# A502D.net
KiCad netlist of a schematic drawn in EAGLE
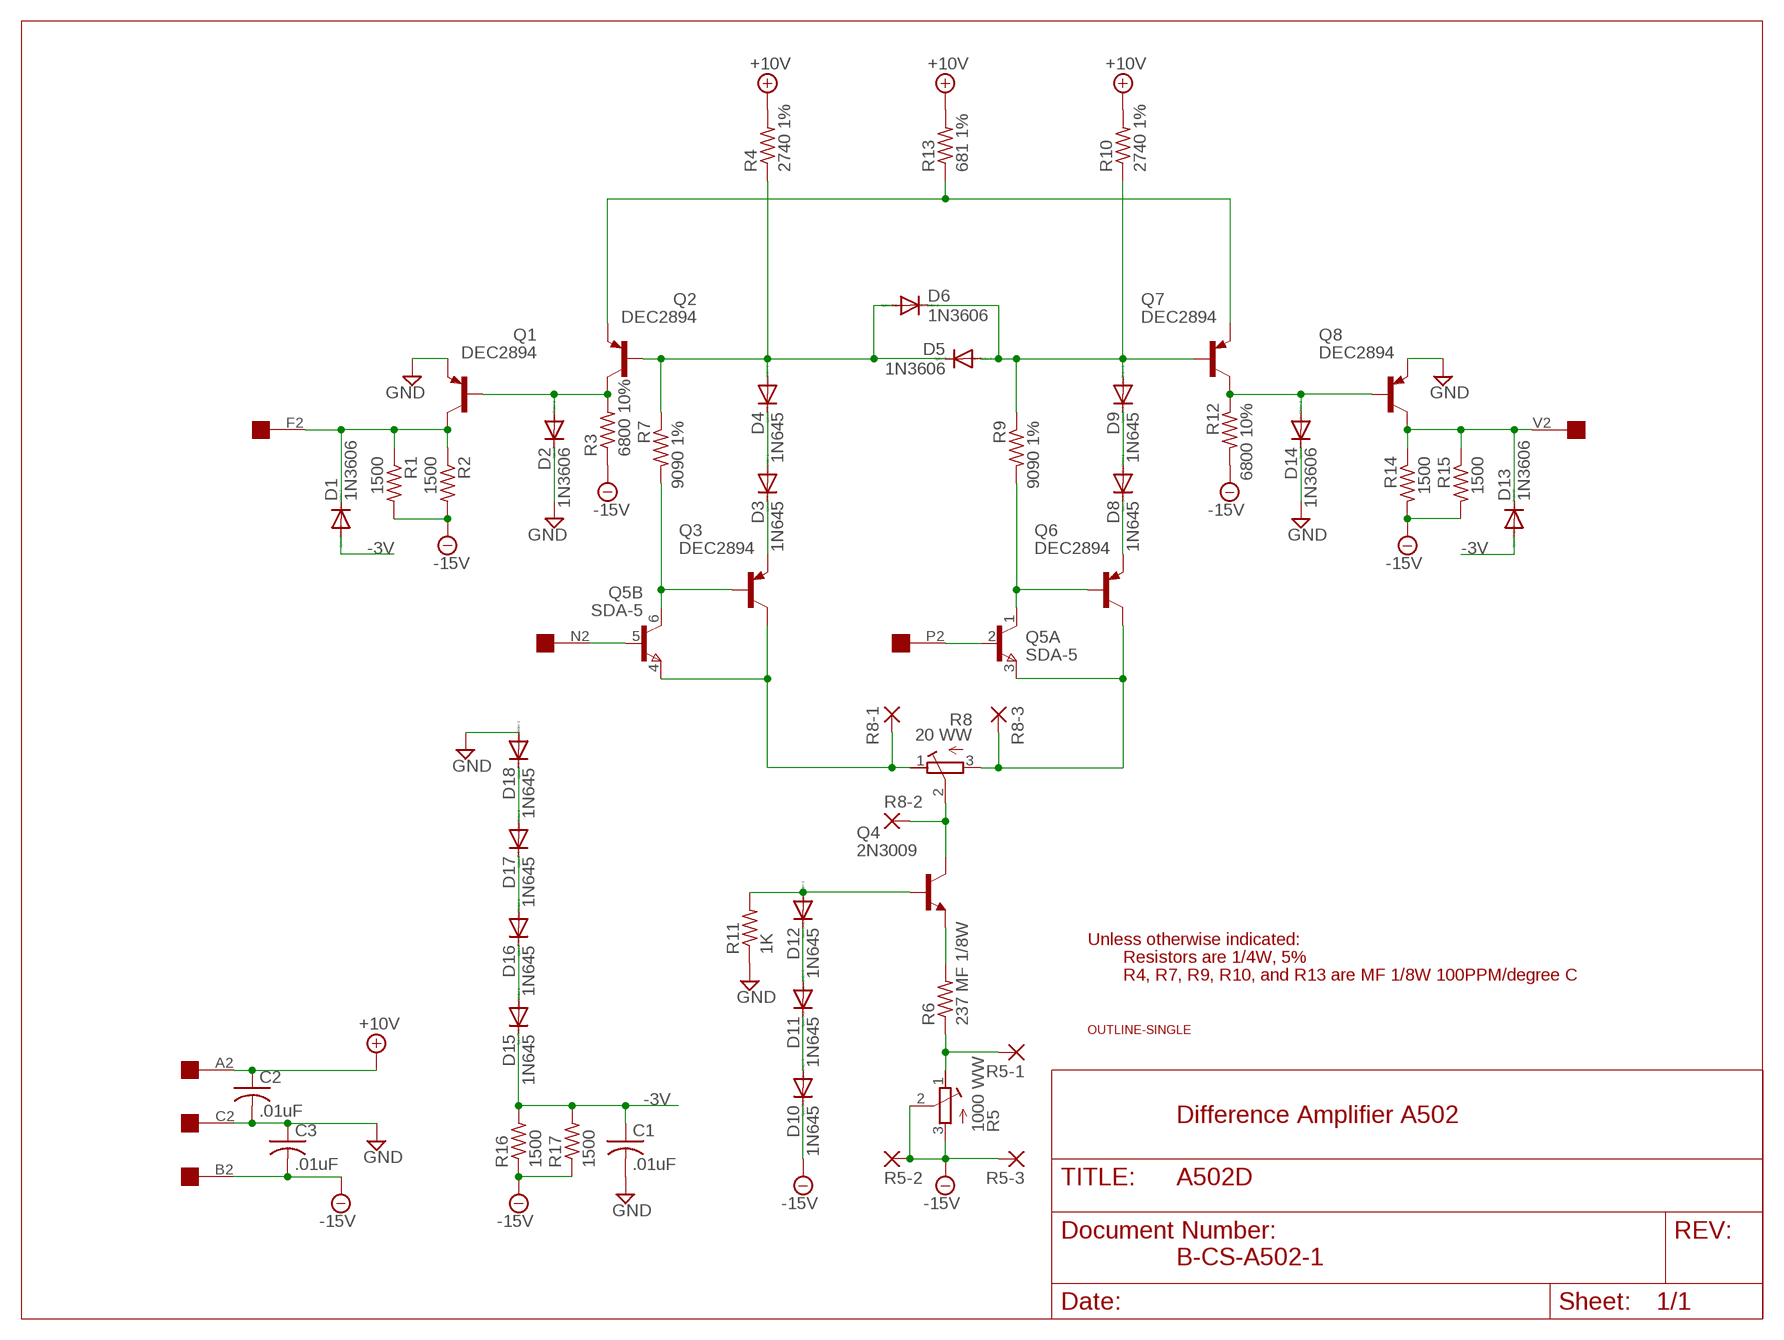
[diagram p0: schematic, sheet 1]

(export (version "E")
  (design (tool "Eeschema 10.0.6"))
  (components
    (comp (ref "C1")
      (value ".01uF")
      (footprint "eagle-import:C050-025X075")
      (libsource (lib "eagle-import") (part "C-US050-025X075"))
    )
    (comp (ref "C2")
      (value ".01uF")
      (footprint "eagle-import:C050-025X075")
      (libsource (lib "eagle-import") (part "C-US050-025X075"))
    )
    (comp (ref "C3")
      (value ".01uF")
      (footprint "eagle-import:C050-025X075")
      (libsource (lib "eagle-import") (part "C-US050-025X075"))
    )
    (comp (ref "D1")
      (value "1N3606")
      (footprint "eagle-import:DO35-10")
      (libsource (lib "eagle-import") (part "1N4148DO35-10"))
    )
    (comp (ref "D2")
      (value "1N3606")
      (footprint "eagle-import:DO35-10")
      (libsource (lib "eagle-import") (part "1N4148DO35-10"))
    )
    (comp (ref "D3")
      (value "1N645")
      (footprint "eagle-import:DO35-10")
      (libsource (lib "eagle-import") (part "1N4148DO35-10"))
    )
    (comp (ref "D4")
      (value "1N645")
      (footprint "eagle-import:DO35-10")
      (libsource (lib "eagle-import") (part "1N4148DO35-10"))
    )
    (comp (ref "D5")
      (value "1N3606")
      (footprint "eagle-import:DO35-10")
      (libsource (lib "eagle-import") (part "1N4148DO35-10"))
    )
    (comp (ref "D6")
      (value "1N3606")
      (footprint "eagle-import:DO35-10")
      (libsource (lib "eagle-import") (part "1N4148DO35-10"))
    )
    (comp (ref "D8")
      (value "1N645")
      (footprint "eagle-import:DO35-10")
      (libsource (lib "eagle-import") (part "1N4148DO35-10"))
    )
    (comp (ref "D9")
      (value "1N645")
      (footprint "eagle-import:DO35-10")
      (libsource (lib "eagle-import") (part "1N4148DO35-10"))
    )
    (comp (ref "D10")
      (value "1N645")
      (footprint "eagle-import:DO35-10")
      (libsource (lib "eagle-import") (part "1N4148DO35-10"))
    )
    (comp (ref "D11")
      (value "1N645")
      (footprint "eagle-import:DO35-10")
      (libsource (lib "eagle-import") (part "1N4148DO35-10"))
    )
    (comp (ref "D12")
      (value "1N645")
      (footprint "eagle-import:DO35-10")
      (libsource (lib "eagle-import") (part "1N4148DO35-10"))
    )
    (comp (ref "D13")
      (value "1N3606")
      (footprint "eagle-import:DO35-10")
      (libsource (lib "eagle-import") (part "1N4148DO35-10"))
    )
    (comp (ref "D14")
      (value "1N3606")
      (footprint "eagle-import:DO35-10")
      (libsource (lib "eagle-import") (part "1N4148DO35-10"))
    )
    (comp (ref "D15")
      (value "1N645")
      (footprint "eagle-import:DO35-10")
      (libsource (lib "eagle-import") (part "1N4148DO35-10"))
    )
    (comp (ref "D16")
      (value "1N645")
      (footprint "eagle-import:DO35-10")
      (libsource (lib "eagle-import") (part "1N4148DO35-10"))
    )
    (comp (ref "D17")
      (value "1N645")
      (footprint "eagle-import:DO35-10")
      (libsource (lib "eagle-import") (part "1N4148DO35-10"))
    )
    (comp (ref "D18")
      (value "1N645")
      (footprint "eagle-import:DO35-10")
      (libsource (lib "eagle-import") (part "1N4148DO35-10"))
    )
    (comp (ref "Q1")
      (value "DEC2894")
      (footprint "eagle-import:TO39")
      (libsource (lib "eagle-import") (part "2N2904A"))
    )
    (comp (ref "Q2")
      (value "DEC2894")
      (footprint "eagle-import:TO39")
      (libsource (lib "eagle-import") (part "2N2904A"))
    )
    (comp (ref "Q3")
      (value "DEC2894")
      (footprint "eagle-import:TO39")
      (libsource (lib "eagle-import") (part "2N2904A"))
    )
    (comp (ref "Q4")
      (value "2N3009")
      (footprint "eagle-import:TO5")
      (libsource (lib "eagle-import") (part "2N2219"))
    )
    (comp (ref "Q5")
      (value "SDA-5")
      (footprint "eagle-import:TO78")
      (libsource (lib "eagle-import") (part "MAT-02H"))
    )
    (comp (ref "Q6")
      (value "DEC2894")
      (footprint "eagle-import:TO39")
      (libsource (lib "eagle-import") (part "2N2904A"))
    )
    (comp (ref "Q7")
      (value "DEC2894")
      (footprint "eagle-import:TO39")
      (libsource (lib "eagle-import") (part "2N2904A"))
    )
    (comp (ref "Q8")
      (value "DEC2894")
      (footprint "eagle-import:TO39")
      (libsource (lib "eagle-import") (part "2N2904A"))
    )
    (comp (ref "R1")
      (value "1500")
      (footprint "eagle-import:0207_10")
      (libsource (lib "eagle-import") (part "R-US_0207/10"))
    )
    (comp (ref "R2")
      (value "1500")
      (footprint "eagle-import:0207_10")
      (libsource (lib "eagle-import") (part "R-US_0207/10"))
    )
    (comp (ref "R3")
      (value "6800 10%")
      (footprint "eagle-import:0207_10")
      (libsource (lib "eagle-import") (part "R-US_0207/10"))
    )
    (comp (ref "R4")
      (value "2740 1%")
      (footprint "eagle-import:0207_15")
      (libsource (lib "eagle-import") (part "R-US_0207/15"))
    )
    (comp (ref "R5")
      (value "1000 WW")
      (footprint "eagle-import:3006Y")
      (libsource (lib "eagle-import") (part "275P"))
    )
    (comp (ref "R5-1")
      (value "2,54/0,8")
      (footprint "eagle-import:2,54_0,8")
      (libsource (lib "eagle-import") (part "2,54/0,8"))
    )
    (comp (ref "R5-2")
      (value "2,54/0,8")
      (footprint "eagle-import:2,54_0,8")
      (libsource (lib "eagle-import") (part "2,54/0,8"))
    )
    (comp (ref "R5-3")
      (value "2,54/0,8")
      (footprint "eagle-import:2,54_0,8")
      (libsource (lib "eagle-import") (part "2,54/0,8"))
    )
    (comp (ref "R6")
      (value "237 MF 1/8W")
      (footprint "eagle-import:0207_15")
      (libsource (lib "eagle-import") (part "R-US_0207/15"))
    )
    (comp (ref "R7")
      (value "9090 1%")
      (footprint "eagle-import:0207_15")
      (libsource (lib "eagle-import") (part "R-US_0207/15"))
    )
    (comp (ref "R8")
      (value "20 WW")
      (footprint "eagle-import:3006Y")
      (libsource (lib "eagle-import") (part "275P"))
    )
    (comp (ref "R8-1")
      (value "2,54/0,8")
      (footprint "eagle-import:2,54_0,8")
      (libsource (lib "eagle-import") (part "2,54/0,8"))
    )
    (comp (ref "R8-2")
      (value "2,54/0,8")
      (footprint "eagle-import:2,54_0,8")
      (libsource (lib "eagle-import") (part "2,54/0,8"))
    )
    (comp (ref "R8-3")
      (value "2,54/0,8")
      (footprint "eagle-import:2,54_0,8")
      (libsource (lib "eagle-import") (part "2,54/0,8"))
    )
    (comp (ref "R9")
      (value "9090 1%")
      (footprint "eagle-import:0207_15")
      (libsource (lib "eagle-import") (part "R-US_0207/15"))
    )
    (comp (ref "R10")
      (value "2740 1%")
      (footprint "eagle-import:0207_15")
      (libsource (lib "eagle-import") (part "R-US_0207/15"))
    )
    (comp (ref "R11")
      (value "1K")
      (footprint "eagle-import:0207_10")
      (libsource (lib "eagle-import") (part "R-US_0207/10"))
    )
    (comp (ref "R12")
      (value "6800 10%")
      (footprint "eagle-import:0207_10")
      (libsource (lib "eagle-import") (part "R-US_0207/10"))
    )
    (comp (ref "R13")
      (value "681 1%")
      (footprint "eagle-import:0207_15")
      (libsource (lib "eagle-import") (part "R-US_0207/15"))
    )
    (comp (ref "R14")
      (value "1500")
      (footprint "eagle-import:0207_10")
      (libsource (lib "eagle-import") (part "R-US_0207/10"))
    )
    (comp (ref "R15")
      (value "1500")
      (footprint "eagle-import:0207_10")
      (libsource (lib "eagle-import") (part "R-US_0207/10"))
    )
    (comp (ref "R16")
      (value "1500")
      (footprint "eagle-import:0207_10")
      (libsource (lib "eagle-import") (part "R-US_0207/10"))
    )
    (comp (ref "R17")
      (value "1500")
      (footprint "eagle-import:0207_10")
      (libsource (lib "eagle-import") (part "R-US_0207/10"))
    )
    (comp (ref "U$2")
      (value "OUTLINE-SINGLE")
      (footprint "eagle-import:SINGLE")
      (libsource (lib "eagle-import") (part "OUTLINE-SINGLE"))
    )
    (comp (ref "U$3")
      (value "EDGE-1")
      (footprint "eagle-import:EDGE-CON1")
      (libsource (lib "eagle-import") (part "EDGE-1"))
    )
  )
  (nets
    (net (code "1") (name "+10V") (class "Default")
      (node (ref "C2") (pin "1") (pinfunction "1_1") (pintype "passive"))
      (node (ref "R10") (pin "2") (pinfunction "2_2") (pintype "passive"))
      (node (ref "R13") (pin "2") (pinfunction "2_2") (pintype "passive"))
      (node (ref "R4") (pin "2") (pinfunction "2_2") (pintype "passive"))
      (node (ref "U$3") (pin "A2") (pinfunction "1_A2") (pintype "bidirectional"))
    )
    (net (code "2") (name "-15V") (class "Default")
      (node (ref "C3") (pin "2") (pinfunction "2_2") (pintype "passive"))
      (node (ref "D10") (pin "C") (pinfunction "C_C") (pintype "passive"))
      (node (ref "R1") (pin "2") (pinfunction "2_2") (pintype "passive"))
      (node (ref "R12") (pin "2") (pinfunction "2_2") (pintype "passive"))
      (node (ref "R14") (pin "2") (pinfunction "2_2") (pintype "passive"))
      (node (ref "R15") (pin "2") (pinfunction "2_2") (pintype "passive"))
      (node (ref "R16") (pin "1") (pinfunction "1_1") (pintype "passive"))
      (node (ref "R17") (pin "1") (pinfunction "1_1") (pintype "passive"))
      (node (ref "R2") (pin "2") (pinfunction "2_2") (pintype "passive"))
      (node (ref "R3") (pin "1") (pinfunction "1_1") (pintype "passive"))
      (node (ref "R5") (pin "2") (pinfunction "S_2") (pintype "passive"))
      (node (ref "R5") (pin "3") (pinfunction "E_3") (pintype "passive"))
      (node (ref "R5-2") (pin "1") (pinfunction "P_1") (pintype "passive"))
      (node (ref "R5-3") (pin "1") (pinfunction "P_1") (pintype "passive"))
      (node (ref "U$3") (pin "B2") (pinfunction "1_B2") (pintype "bidirectional"))
    )
    (net (code "3") (name "/-3V") (class "Default")
      (node (ref "C1") (pin "1") (pinfunction "1_1") (pintype "passive"))
      (node (ref "D1") (pin "A") (pinfunction "A_A") (pintype "passive"))
      (node (ref "D13") (pin "A") (pinfunction "A_A") (pintype "passive"))
      (node (ref "D15") (pin "C") (pinfunction "C_C") (pintype "passive"))
      (node (ref "R16") (pin "2") (pinfunction "2_2") (pintype "passive"))
      (node (ref "R17") (pin "2") (pinfunction "2_2") (pintype "passive"))
    )
    (net (code "4") (name "GND") (class "Default")
      (node (ref "C1") (pin "2") (pinfunction "2_2") (pintype "passive"))
      (node (ref "C2") (pin "2") (pinfunction "2_2") (pintype "passive"))
      (node (ref "C3") (pin "1") (pinfunction "1_1") (pintype "passive"))
      (node (ref "D14") (pin "C") (pinfunction "C_C") (pintype "passive"))
      (node (ref "D18") (pin "A") (pinfunction "A_A") (pintype "passive"))
      (node (ref "D2") (pin "C") (pinfunction "C_C") (pintype "passive"))
      (node (ref "Q1") (pin "1") (pinfunction "E_1") (pintype "passive"))
      (node (ref "Q8") (pin "1") (pinfunction "E_1") (pintype "passive"))
      (node (ref "R11") (pin "1") (pinfunction "1_1") (pintype "passive"))
      (node (ref "U$3") (pin "C2") (pinfunction "1_C2") (pintype "bidirectional"))
    )
    (net (code "5") (name "Net-(D3-PadA)") (class "Default")
      (node (ref "D3") (pin "A") (pinfunction "A_A") (pintype "passive"))
      (node (ref "D4") (pin "C") (pinfunction "C_C") (pintype "passive"))
    )
    (net (code "6") (name "Net-(D8-PadA)") (class "Default")
      (node (ref "D8") (pin "A") (pinfunction "A_A") (pintype "passive"))
      (node (ref "D9") (pin "C") (pinfunction "C_C") (pintype "passive"))
    )
    (net (code "7") (name "Net-(D10-PadA)") (class "Default")
      (node (ref "D10") (pin "A") (pinfunction "A_A") (pintype "passive"))
      (node (ref "D11") (pin "C") (pinfunction "C_C") (pintype "passive"))
    )
    (net (code "8") (name "Net-(D11-PadA)") (class "Default")
      (node (ref "D11") (pin "A") (pinfunction "A_A") (pintype "passive"))
      (node (ref "D12") (pin "C") (pinfunction "C_C") (pintype "passive"))
    )
    (net (code "9") (name "Net-(D15-PadA)") (class "Default")
      (node (ref "D15") (pin "A") (pinfunction "A_A") (pintype "passive"))
      (node (ref "D16") (pin "C") (pinfunction "C_C") (pintype "passive"))
    )
    (net (code "10") (name "Net-(D16-PadA)") (class "Default")
      (node (ref "D16") (pin "A") (pinfunction "A_A") (pintype "passive"))
      (node (ref "D17") (pin "C") (pinfunction "C_C") (pintype "passive"))
    )
    (net (code "11") (name "Net-(D17-PadA)") (class "Default")
      (node (ref "D17") (pin "A") (pinfunction "A_A") (pintype "passive"))
      (node (ref "D18") (pin "C") (pinfunction "C_C") (pintype "passive"))
    )
    (net (code "12") (name "Net-(Q1-B)") (class "Default")
      (node (ref "D2") (pin "A") (pinfunction "A_A") (pintype "passive"))
      (node (ref "Q1") (pin "2") (pinfunction "B_2") (pintype "passive"))
      (node (ref "Q2") (pin "3") (pinfunction "C_3") (pintype "passive"))
      (node (ref "R3") (pin "2") (pinfunction "2_2") (pintype "passive"))
    )
    (net (code "13") (name "Net-(Q1-C)") (class "Default")
      (node (ref "D1") (pin "C") (pinfunction "C_C") (pintype "passive"))
      (node (ref "Q1") (pin "3") (pinfunction "C_3") (pintype "passive"))
      (node (ref "R1") (pin "1") (pinfunction "1_1") (pintype "passive"))
      (node (ref "R2") (pin "1") (pinfunction "1_1") (pintype "passive"))
      (node (ref "U$3") (pin "F2") (pinfunction "1_F2") (pintype "bidirectional"))
    )
    (net (code "14") (name "Net-(Q2-B)") (class "Default")
      (node (ref "D4") (pin "A") (pinfunction "A_A") (pintype "passive"))
      (node (ref "D5") (pin "C") (pinfunction "C_C") (pintype "passive"))
      (node (ref "D6") (pin "A") (pinfunction "A_A") (pintype "passive"))
      (node (ref "Q2") (pin "2") (pinfunction "B_2") (pintype "passive"))
      (node (ref "R4") (pin "1") (pinfunction "1_1") (pintype "passive"))
      (node (ref "R7") (pin "1") (pinfunction "1_1") (pintype "passive"))
    )
    (net (code "15") (name "Net-(Q2-E)") (class "Default")
      (node (ref "Q2") (pin "1") (pinfunction "E_1") (pintype "passive"))
      (node (ref "Q7") (pin "1") (pinfunction "E_1") (pintype "passive"))
      (node (ref "R13") (pin "1") (pinfunction "1_1") (pintype "passive"))
    )
    (net (code "16") (name "Net-(Q3-B)") (class "Default")
      (node (ref "Q3") (pin "2") (pinfunction "B_2") (pintype "passive"))
      (node (ref "Q5") (pin "6") (pinfunction "C_6") (pintype "passive"))
      (node (ref "R7") (pin "2") (pinfunction "2_2") (pintype "passive"))
    )
    (net (code "17") (name "Net-(Q3-C)") (class "Default")
      (node (ref "Q3") (pin "3") (pinfunction "C_3") (pintype "passive"))
      (node (ref "Q5") (pin "4") (pinfunction "E_4") (pintype "passive"))
      (node (ref "R8") (pin "1") (pinfunction "A_1") (pintype "passive"))
      (node (ref "R8-1") (pin "1") (pinfunction "P_1") (pintype "passive"))
    )
    (net (code "18") (name "Net-(Q3-E)") (class "Default")
      (node (ref "D3") (pin "C") (pinfunction "C_C") (pintype "passive"))
      (node (ref "Q3") (pin "1") (pinfunction "E_1") (pintype "passive"))
    )
    (net (code "19") (name "Net-(Q4-B)") (class "Default")
      (node (ref "D12") (pin "A") (pinfunction "A_A") (pintype "passive"))
      (node (ref "Q4") (pin "2") (pinfunction "B_2") (pintype "passive"))
      (node (ref "R11") (pin "2") (pinfunction "2_2") (pintype "passive"))
    )
    (net (code "20") (name "Net-(Q4-C)") (class "Default")
      (node (ref "Q4") (pin "3") (pinfunction "C_3") (pintype "passive"))
      (node (ref "R8") (pin "2") (pinfunction "S_2") (pintype "passive"))
      (node (ref "R8-2") (pin "1") (pinfunction "P_1") (pintype "passive"))
    )
    (net (code "21") (name "Net-(Q4-E)") (class "Default")
      (node (ref "Q4") (pin "1") (pinfunction "E_1") (pintype "passive"))
      (node (ref "R6") (pin "2") (pinfunction "2_2") (pintype "passive"))
    )
    (net (code "22") (name "Net-(Q5A-B)") (class "Default")
      (node (ref "Q5") (pin "2") (pinfunction "B_2") (pintype "passive"))
      (node (ref "U$3") (pin "P2") (pinfunction "1_P2") (pintype "bidirectional"))
    )
    (net (code "23") (name "Net-(Q5A-C)") (class "Default")
      (node (ref "Q5") (pin "1") (pinfunction "C_1") (pintype "passive"))
      (node (ref "Q6") (pin "2") (pinfunction "B_2") (pintype "passive"))
      (node (ref "R9") (pin "2") (pinfunction "2_2") (pintype "passive"))
    )
    (net (code "24") (name "Net-(Q5A-E)") (class "Default")
      (node (ref "Q5") (pin "3") (pinfunction "E_3") (pintype "passive"))
      (node (ref "Q6") (pin "3") (pinfunction "C_3") (pintype "passive"))
      (node (ref "R8") (pin "3") (pinfunction "E_3") (pintype "passive"))
      (node (ref "R8-3") (pin "1") (pinfunction "P_1") (pintype "passive"))
    )
    (net (code "25") (name "Net-(Q5B-B)") (class "Default")
      (node (ref "Q5") (pin "5") (pinfunction "B_5") (pintype "passive"))
      (node (ref "U$3") (pin "N2") (pinfunction "1_N2") (pintype "bidirectional"))
    )
    (net (code "26") (name "Net-(Q6-E)") (class "Default")
      (node (ref "D8") (pin "C") (pinfunction "C_C") (pintype "passive"))
      (node (ref "Q6") (pin "1") (pinfunction "E_1") (pintype "passive"))
    )
    (net (code "27") (name "Net-(Q7-B)") (class "Default")
      (node (ref "D5") (pin "A") (pinfunction "A_A") (pintype "passive"))
      (node (ref "D6") (pin "C") (pinfunction "C_C") (pintype "passive"))
      (node (ref "D9") (pin "A") (pinfunction "A_A") (pintype "passive"))
      (node (ref "Q7") (pin "2") (pinfunction "B_2") (pintype "passive"))
      (node (ref "R10") (pin "1") (pinfunction "1_1") (pintype "passive"))
      (node (ref "R9") (pin "1") (pinfunction "1_1") (pintype "passive"))
    )
    (net (code "28") (name "Net-(Q7-C)") (class "Default")
      (node (ref "D14") (pin "A") (pinfunction "A_A") (pintype "passive"))
      (node (ref "Q7") (pin "3") (pinfunction "C_3") (pintype "passive"))
      (node (ref "Q8") (pin "2") (pinfunction "B_2") (pintype "passive"))
      (node (ref "R12") (pin "1") (pinfunction "1_1") (pintype "passive"))
    )
    (net (code "29") (name "Net-(Q8-C)") (class "Default")
      (node (ref "D13") (pin "C") (pinfunction "C_C") (pintype "passive"))
      (node (ref "Q8") (pin "3") (pinfunction "C_3") (pintype "passive"))
      (node (ref "R14") (pin "1") (pinfunction "1_1") (pintype "passive"))
      (node (ref "R15") (pin "1") (pinfunction "1_1") (pintype "passive"))
      (node (ref "U$3") (pin "V2") (pinfunction "1_V2") (pintype "bidirectional"))
    )
    (net (code "30") (name "Net-(R5-1-P)") (class "Default")
      (node (ref "R5") (pin "1") (pinfunction "A_1") (pintype "passive"))
      (node (ref "R5-1") (pin "1") (pinfunction "P_1") (pintype "passive"))
      (node (ref "R6") (pin "1") (pinfunction "1_1") (pintype "passive"))
    )
  )
)
